# Quectel-2560-v2_2.net
KiCad netlist of a schematic drawn in EAGLE
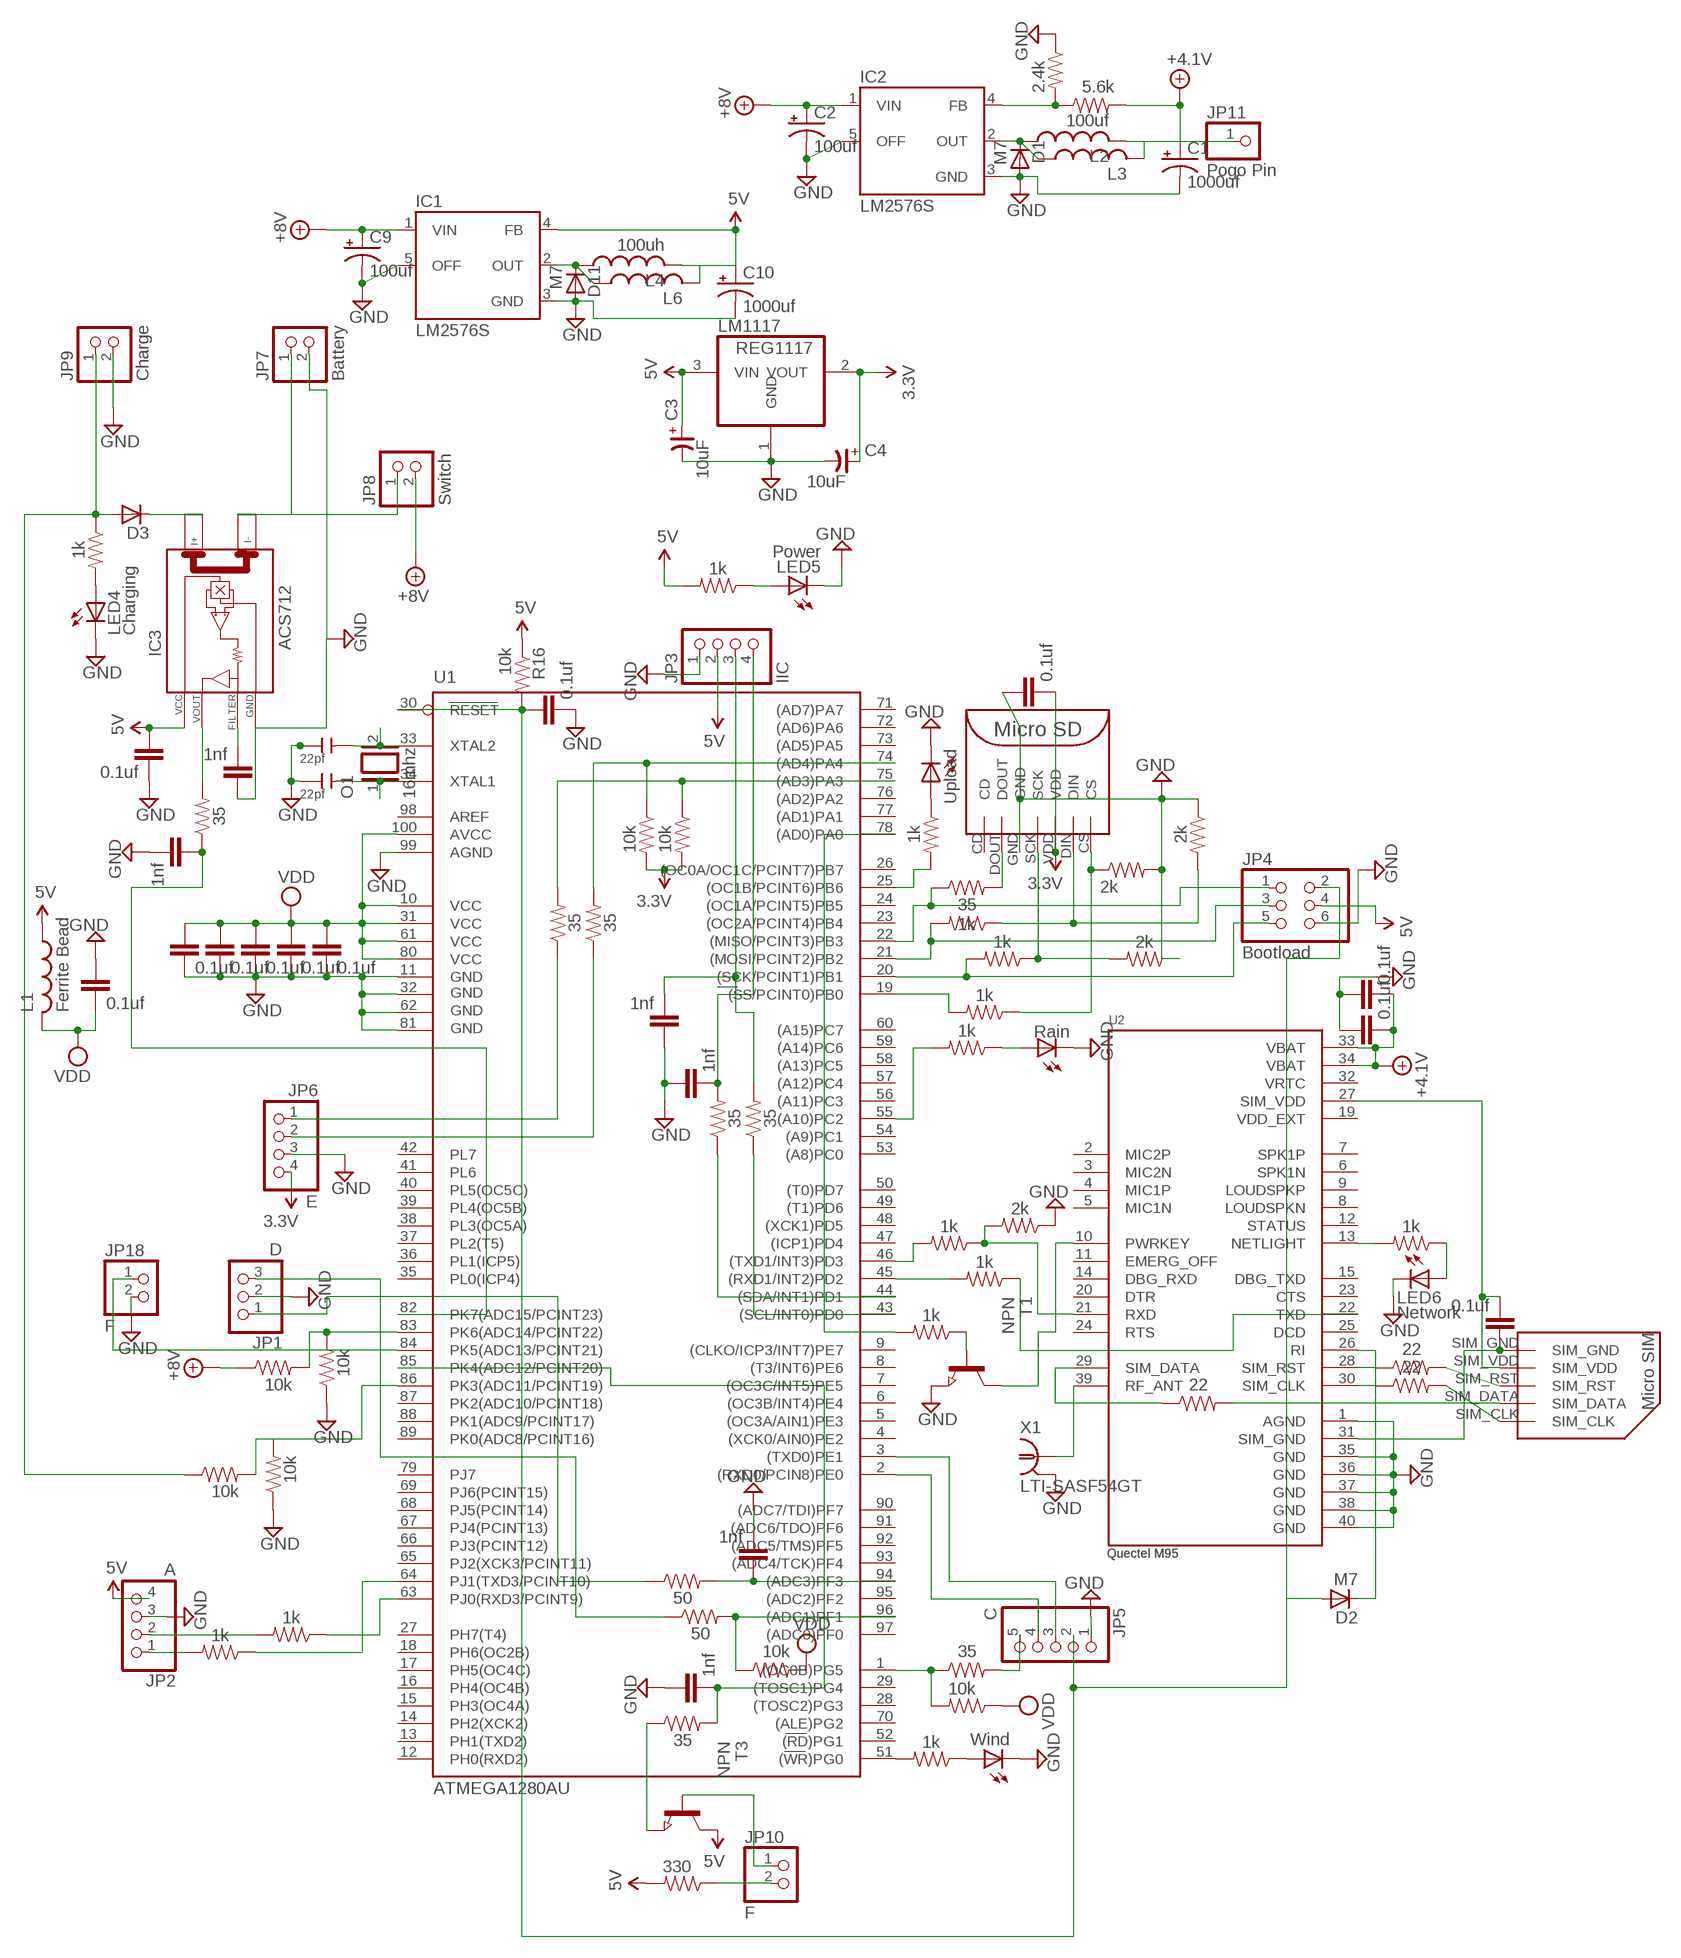
[diagram p0: schematic, sheet 1]

(export (version "E")
  (design (tool "Eeschema 10.0.6"))
  (components
    (comp (ref "C1")
      (value "1000uf")
      (footprint "eagle-import:153CLV-1012")
      (libsource (lib "eagle-import") (part "CPOL-US153CLV-1012"))
    )
    (comp (ref "C2")
      (value "100uf")
      (footprint "eagle-import:CT7343")
      (libsource (lib "eagle-import") (part "CPOL-USCT7343"))
    )
    (comp (ref "C3")
      (value "10uF")
      (footprint "eagle-import:3528_T")
      (libsource (lib "eagle-import") (part "CP-3528"))
    )
    (comp (ref "C4")
      (value "10uF")
      (footprint "eagle-import:3528_T")
      (libsource (lib "eagle-import") (part "CP-3528"))
    )
    (comp (ref "C7")
      (value "22pf")
      (footprint "eagle-import:C0805")
      (fields (field (name "MPN") "CC0805JRNPO9BN220"))
      (libsource (lib "eagle-import") (part "CERAMIC-22PF-50V-5%-NPO(0805)"))
    )
    (comp (ref "C8")
      (value "22pf")
      (footprint "eagle-import:C0805")
      (fields (field (name "MPN") "CC0805JRNPO9BN220"))
      (libsource (lib "eagle-import") (part "CERAMIC-22PF-50V-5%-NPO(0805)"))
    )
    (comp (ref "C9")
      (value "100uf")
      (footprint "eagle-import:CT7343")
      (libsource (lib "eagle-import") (part "CPOL-USCT7343"))
    )
    (comp (ref "C10")
      (value "1000uf")
      (footprint "eagle-import:153CLV-1012")
      (libsource (lib "eagle-import") (part "CPOL-US153CLV-1012"))
    )
    (comp (ref "D1")
      (value "M7")
      (footprint "eagle-import:SOD106A")
      (fields (field (name "MPN") "BYS10/45"))
      (libsource (lib "eagle-import") (part "BYS10"))
    )
    (comp (ref "D2")
      (value "M7")
      (footprint "eagle-import:SOD106A")
      (fields (field (name "MPN") "BYS10/45"))
      (libsource (lib "eagle-import") (part "BYS10"))
    )
    (comp (ref "D3")
      (value "BYS10")
      (footprint "eagle-import:SOD106A")
      (fields (field (name "MPN") "BYS10/45"))
      (libsource (lib "eagle-import") (part "BYS10"))
    )
    (comp (ref "D11")
      (value "M7")
      (footprint "eagle-import:SOD106A")
      (fields (field (name "MPN") "BYS10/45"))
      (libsource (lib "eagle-import") (part "BYS10"))
    )
    (comp (ref "DC1")
      (value "0.1uf")
      (footprint "eagle-import:C0805")
      (libsource (lib "eagle-import") (part "C-EUC0805"))
    )
    (comp (ref "DC2")
      (value "0.1uf")
      (footprint "eagle-import:C0805")
      (libsource (lib "eagle-import") (part "C-EUC0805"))
    )
    (comp (ref "DC3")
      (value "0.1uf")
      (footprint "eagle-import:C0805")
      (libsource (lib "eagle-import") (part "C-EUC0805"))
    )
    (comp (ref "DC4")
      (value "0.1uf")
      (footprint "eagle-import:C0805")
      (libsource (lib "eagle-import") (part "C-EUC0805"))
    )
    (comp (ref "DC5")
      (value "0.1uf")
      (footprint "eagle-import:C0805")
      (libsource (lib "eagle-import") (part "C-EUC0805"))
    )
    (comp (ref "DC6")
      (value "0.1uf")
      (footprint "eagle-import:C0805")
      (libsource (lib "eagle-import") (part "C-EUC0805"))
    )
    (comp (ref "DC7")
      (value "0.1uf")
      (footprint "eagle-import:C0805")
      (libsource (lib "eagle-import") (part "C-EUC0805"))
    )
    (comp (ref "DC10")
      (value "0.1uf")
      (footprint "eagle-import:C0805")
      (libsource (lib "eagle-import") (part "C-EUC0805"))
    )
    (comp (ref "DC11")
      (value "0.1uf")
      (footprint "eagle-import:C0805")
      (libsource (lib "eagle-import") (part "C-EUC0805"))
    )
    (comp (ref "DC12")
      (value "1nf")
      (footprint "eagle-import:C0805")
      (libsource (lib "eagle-import") (part "C-EUC0805"))
    )
    (comp (ref "DC13")
      (value "1nf")
      (footprint "eagle-import:C0805")
      (libsource (lib "eagle-import") (part "C-EUC0805"))
    )
    (comp (ref "DC14")
      (value "1nf")
      (footprint "eagle-import:C0805")
      (libsource (lib "eagle-import") (part "C-EUC0805"))
    )
    (comp (ref "DC15")
      (value "0.1uf")
      (footprint "eagle-import:C0805")
      (libsource (lib "eagle-import") (part "C-EUC0805"))
    )
    (comp (ref "DC17")
      (value "1nf")
      (footprint "eagle-import:C0805")
      (libsource (lib "eagle-import") (part "C-EUC0805"))
    )
    (comp (ref "DC18")
      (value "0.1uf")
      (footprint "eagle-import:C0805")
      (libsource (lib "eagle-import") (part "C-EUC0805"))
    )
    (comp (ref "DC19")
      (value "0.1uf")
      (footprint "eagle-import:C0805")
      (libsource (lib "eagle-import") (part "C-EUC0805"))
    )
    (comp (ref "DC20")
      (value "1nf")
      (footprint "eagle-import:C0805")
      (libsource (lib "eagle-import") (part "C-EUC0805"))
    )
    (comp (ref "DC21")
      (value "1nf")
      (footprint "eagle-import:C0805")
      (libsource (lib "eagle-import") (part "C-EUC0805"))
    )
    (comp (ref "IC1")
      (value "LM2576S")
      (footprint "eagle-import:TO263-5")
      (libsource (lib "eagle-import") (part "LM2576S"))
    )
    (comp (ref "IC2")
      (value "LM2576S")
      (footprint "eagle-import:TO263-5")
      (libsource (lib "eagle-import") (part "LM2576S"))
    )
    (comp (ref "IC3")
      (value "ACS712")
      (footprint "eagle-import:SO08")
      (libsource (lib "eagle-import") (part "ACS712"))
    )
    (comp (ref "JP1")
      (value "D")
      (footprint "eagle-import:1X03")
      (libsource (lib "eagle-import") (part "PINHD-1X3"))
    )
    (comp (ref "JP2")
      (value "A")
      (footprint "eagle-import:1X04")
      (libsource (lib "eagle-import") (part "PINHD-1X4"))
    )
    (comp (ref "JP3")
      (value "IIC")
      (footprint "eagle-import:1X04")
      (libsource (lib "eagle-import") (part "PINHD-1X4"))
    )
    (comp (ref "JP4")
      (value "Bootload")
      (footprint "eagle-import:2X03")
      (libsource (lib "eagle-import") (part "PINHD-2X3"))
    )
    (comp (ref "JP5")
      (value "C")
      (footprint "eagle-import:1X05")
      (libsource (lib "eagle-import") (part "PINHD-1X5"))
    )
    (comp (ref "JP6")
      (value "E")
      (footprint "eagle-import:1X04")
      (libsource (lib "eagle-import") (part "PINHD-1X4"))
    )
    (comp (ref "JP7")
      (value "Battery")
      (footprint "eagle-import:1X02")
      (libsource (lib "eagle-import") (part "PINHD-1X2"))
    )
    (comp (ref "JP8")
      (value "Switch")
      (footprint "eagle-import:1X02")
      (libsource (lib "eagle-import") (part "PINHD-1X2"))
    )
    (comp (ref "JP9")
      (value "Charge")
      (footprint "eagle-import:1X02")
      (libsource (lib "eagle-import") (part "PINHD-1X2"))
    )
    (comp (ref "JP10")
      (value "F")
      (footprint "eagle-import:1X02")
      (libsource (lib "eagle-import") (part "PINHD-1X2"))
    )
    (comp (ref "JP11")
      (value "Pogo Pin")
      (footprint "eagle-import:1X01")
      (libsource (lib "eagle-import") (part "PINHD-1X1"))
    )
    (comp (ref "JP18")
      (value "F")
      (footprint "eagle-import:1X02")
      (libsource (lib "eagle-import") (part "PINHD-1X2"))
    )
    (comp (ref "L1")
      (value "Ferrite Bead")
      (footprint "eagle-import:L2012C")
      (libsource (lib "eagle-import") (part "L-USL2012C"))
    )
    (comp (ref "L2")
      (value "100uf")
      (footprint "eagle-import:PIS2816")
      (libsource (lib "eagle-import") (part "L-USPIS2816"))
    )
    (comp (ref "L3")
      (value "L-US6000-XXX-RC")
      (footprint "eagle-import:6000-XXXX-RC")
      (libsource (lib "eagle-import") (part "L-US6000-XXX-RC"))
    )
    (comp (ref "L4")
      (value "100uh")
      (footprint "eagle-import:PIS2816")
      (libsource (lib "eagle-import") (part "L-USPIS2816"))
    )
    (comp (ref "L6")
      (value "L-US6000-XXX-RC")
      (footprint "eagle-import:6000-XXXX-RC")
      (libsource (lib "eagle-import") (part "L-US6000-XXX-RC"))
    )
    (comp (ref "LED1")
      (value "Rain")
      (footprint "eagle-import:CHIP-LED0805")
      (libsource (lib "eagle-import") (part "LEDCHIP-LED0805"))
    )
    (comp (ref "LED2")
      (value "Upload")
      (footprint "eagle-import:CHIP-LED0805")
      (libsource (lib "eagle-import") (part "LEDCHIP-LED0805"))
    )
    (comp (ref "LED3")
      (value "Wind")
      (footprint "eagle-import:CHIP-LED0805")
      (libsource (lib "eagle-import") (part "LEDCHIP-LED0805"))
    )
    (comp (ref "LED4")
      (value "Charging")
      (footprint "eagle-import:CHIP-LED0805")
      (libsource (lib "eagle-import") (part "LEDCHIP-LED0805"))
    )
    (comp (ref "LED5")
      (value "Power")
      (footprint "eagle-import:CHIP-LED0805")
      (libsource (lib "eagle-import") (part "LEDCHIP-LED0805"))
    )
    (comp (ref "LED6")
      (value "Network")
      (footprint "eagle-import:CHIP-LED0805")
      (libsource (lib "eagle-import") (part "LEDCHIP-LED0805"))
    )
    (comp (ref "LM1117")
      (value "REG1117")
      (footprint "eagle-import:SOT223")
      (libsource (lib "eagle-import") (part "REG1117"))
    )
    (comp (ref "O1")
      (value "16mhz")
      (footprint "eagle-import:QS")
      (libsource (lib "eagle-import") (part "XTAL/S"))
    )
    (comp (ref "R1")
      (value "35")
      (footprint "eagle-import:0805")
      (libsource (lib "eagle-import") (part "RESISTOR0805-RES"))
    )
    (comp (ref "R2")
      (value "10k")
      (footprint "eagle-import:0805")
      (libsource (lib "eagle-import") (part "RESISTOR0805-RES"))
    )
    (comp (ref "R3")
      (value "10k")
      (footprint "eagle-import:0805")
      (libsource (lib "eagle-import") (part "RESISTOR0805-RES"))
    )
    (comp (ref "R4")
      (value "1k")
      (footprint "eagle-import:0805")
      (libsource (lib "eagle-import") (part "RESISTOR0805-RES"))
    )
    (comp (ref "R5")
      (value "35")
      (footprint "eagle-import:0805")
      (libsource (lib "eagle-import") (part "RESISTOR0805-RES"))
    )
    (comp (ref "R6")
      (value "1k")
      (footprint "eagle-import:0805")
      (libsource (lib "eagle-import") (part "RESISTOR0805-RES"))
    )
    (comp (ref "R7")
      (value "1k")
      (footprint "eagle-import:0805")
      (libsource (lib "eagle-import") (part "RESISTOR0805-RES"))
    )
    (comp (ref "R8")
      (value "1k")
      (footprint "eagle-import:0805")
      (libsource (lib "eagle-import") (part "RESISTOR0805-RES"))
    )
    (comp (ref "R9")
      (value "2k")
      (footprint "eagle-import:0805")
      (libsource (lib "eagle-import") (part "RESISTOR0805-RES"))
    )
    (comp (ref "R10")
      (value "22")
      (footprint "eagle-import:0805")
      (libsource (lib "eagle-import") (part "RESISTOR0805-RES"))
    )
    (comp (ref "R11")
      (value "22")
      (footprint "eagle-import:0805")
      (libsource (lib "eagle-import") (part "RESISTOR0805-RES"))
    )
    (comp (ref "R14")
      (value "1k")
      (footprint "eagle-import:0805")
      (libsource (lib "eagle-import") (part "RESISTOR0805-RES"))
    )
    (comp (ref "R15")
      (value "1k")
      (footprint "eagle-import:0805")
      (libsource (lib "eagle-import") (part "RESISTOR0805-RES"))
    )
    (comp (ref "R16")
      (value "10k")
      (footprint "eagle-import:0805")
      (libsource (lib "eagle-import") (part "RESISTOR0805-RES"))
    )
    (comp (ref "R17")
      (value "1k")
      (footprint "eagle-import:0805")
      (libsource (lib "eagle-import") (part "RESISTOR0805-RES"))
    )
    (comp (ref "R18")
      (value "1k")
      (footprint "eagle-import:0805")
      (libsource (lib "eagle-import") (part "RESISTOR0805-RES"))
    )
    (comp (ref "R19")
      (value "35")
      (footprint "eagle-import:0805")
      (libsource (lib "eagle-import") (part "RESISTOR0805-RES"))
    )
    (comp (ref "R20")
      (value "10k")
      (footprint "eagle-import:0805")
      (libsource (lib "eagle-import") (part "RESISTOR0805-RES"))
    )
    (comp (ref "R21")
      (value "50")
      (footprint "eagle-import:0805")
      (libsource (lib "eagle-import") (part "RESISTOR0805-RES"))
    )
    (comp (ref "R22")
      (value "35")
      (footprint "eagle-import:0805")
      (libsource (lib "eagle-import") (part "RESISTOR0805-RES"))
    )
    (comp (ref "R23")
      (value "2k")
      (footprint "eagle-import:0805")
      (libsource (lib "eagle-import") (part "RESISTOR0805-RES"))
    )
    (comp (ref "R24")
      (value "2k")
      (footprint "eagle-import:0805")
      (libsource (lib "eagle-import") (part "RESISTOR0805-RES"))
    )
    (comp (ref "R25")
      (value "1k")
      (footprint "eagle-import:0805")
      (libsource (lib "eagle-import") (part "RESISTOR0805-RES"))
    )
    (comp (ref "R26")
      (value "1k")
      (footprint "eagle-import:0805")
      (libsource (lib "eagle-import") (part "RESISTOR0805-RES"))
    )
    (comp (ref "R27")
      (value "1k")
      (footprint "eagle-import:0805")
      (libsource (lib "eagle-import") (part "RESISTOR0805-RES"))
    )
    (comp (ref "R28")
      (value "1k")
      (footprint "eagle-import:0805")
      (libsource (lib "eagle-import") (part "RESISTOR0805-RES"))
    )
    (comp (ref "R29")
      (value "2k")
      (footprint "eagle-import:0805")
      (libsource (lib "eagle-import") (part "RESISTOR0805-RES"))
    )
    (comp (ref "R30")
      (value "35")
      (footprint "eagle-import:0805")
      (libsource (lib "eagle-import") (part "RESISTOR0805-RES"))
    )
    (comp (ref "R31")
      (value "50")
      (footprint "eagle-import:0805")
      (libsource (lib "eagle-import") (part "RESISTOR0805-RES"))
    )
    (comp (ref "R32")
      (value "1k")
      (footprint "eagle-import:0805")
      (libsource (lib "eagle-import") (part "RESISTOR0805-RES"))
    )
    (comp (ref "R33")
      (value "1k")
      (footprint "eagle-import:0805")
      (libsource (lib "eagle-import") (part "RESISTOR0805-RES"))
    )
    (comp (ref "R34")
      (value "10k")
      (footprint "eagle-import:0805")
      (libsource (lib "eagle-import") (part "RESISTOR0805-RES"))
    )
    (comp (ref "R35")
      (value "35")
      (footprint "eagle-import:0805")
      (libsource (lib "eagle-import") (part "RESISTOR0805-RES"))
    )
    (comp (ref "R36")
      (value "10k")
      (footprint "eagle-import:0805")
      (libsource (lib "eagle-import") (part "RESISTOR0805-RES"))
    )
    (comp (ref "R39")
      (value "35")
      (footprint "eagle-import:0805")
      (libsource (lib "eagle-import") (part "RESISTOR0805-RES"))
    )
    (comp (ref "R40")
      (value "10k")
      (footprint "eagle-import:0805")
      (libsource (lib "eagle-import") (part "RESISTOR0805-RES"))
    )
    (comp (ref "R41")
      (value "330")
      (footprint "eagle-import:0805")
      (libsource (lib "eagle-import") (part "RESISTOR0805-RES"))
    )
    (comp (ref "R42")
      (value "35")
      (footprint "eagle-import:0805")
      (libsource (lib "eagle-import") (part "RESISTOR0805-RES"))
    )
    (comp (ref "R43")
      (value "10k")
      (footprint "eagle-import:0805")
      (libsource (lib "eagle-import") (part "RESISTOR0805-RES"))
    )
    (comp (ref "R44")
      (value "10k")
      (footprint "eagle-import:0805")
      (libsource (lib "eagle-import") (part "RESISTOR0805-RES"))
    )
    (comp (ref "R45")
      (value "2.4k")
      (footprint "eagle-import:0805")
      (libsource (lib "eagle-import") (part "RESISTOR0805-RES"))
    )
    (comp (ref "R46")
      (value "5.6k")
      (footprint "eagle-import:0805")
      (libsource (lib "eagle-import") (part "RESISTOR0805-RES"))
    )
    (comp (ref "R47")
      (value "22")
      (footprint "eagle-import:0805")
      (libsource (lib "eagle-import") (part "RESISTOR0805-RES"))
    )
    (comp (ref "T1")
      (value "NPN")
      (footprint "eagle-import:SOT23")
      (libsource (lib "eagle-import") (part "NPN-TRANSISTOR_SOT23"))
    )
    (comp (ref "T3")
      (value "NPN")
      (footprint "eagle-import:SOT23")
      (libsource (lib "eagle-import") (part "NPN-TRANSISTOR_SOT23"))
    )
    (comp (ref "U$1")
      (value "MICROSD")
      (footprint "eagle-import:MICROSD")
      (libsource (lib "eagle-import") (part "MICROSD"))
    )
    (comp (ref "U$2")
      (value "MICROSIM")
      (footprint "eagle-import:MICROSIM")
      (libsource (lib "eagle-import") (part "MICROSIM"))
    )
    (comp (ref "U1")
      (value "ATMEGA1280AU")
      (footprint "eagle-import:TQFP100")
      (libsource (lib "eagle-import") (part "ATMEGA2560AU"))
    )
    (comp (ref "U2")
      (value "Quectel M95")
      (footprint "eagle-import:XCVR_M95")
      (libsource (lib "eagle-import") (part "M95"))
    )
    (comp (ref "X1")
      (value "LTI-SASF54GT")
      (footprint "eagle-import:LTI-SASF54GT")
      (libsource (lib "eagle-import") (part "LTI-SASF54GT"))
    )
  )
  (nets
    (net (code "1") (name "+4.1V") (class "Default")
      (node (ref "C1") (pin "+") (pinfunction "+_+") (pintype "passive"))
      (node (ref "DC6") (pin "2") (pinfunction "2_2") (pintype "passive"))
      (node (ref "DC7") (pin "2") (pinfunction "2_2") (pintype "passive"))
      (node (ref "JP11") (pin "1") (pinfunction "1_1") (pintype "passive"))
      (node (ref "L2") (pin "2") (pinfunction "2_2") (pintype "passive"))
      (node (ref "L3") (pin "2") (pinfunction "2_2") (pintype "passive"))
      (node (ref "R46") (pin "2") (pinfunction "2_2") (pintype "passive"))
      (node (ref "U2") (pin "33") (pinfunction "VBAT_33") (pintype "power_in"))
      (node (ref "U2") (pin "34") (pinfunction "VBAT_34") (pintype "power_in"))
    )
    (net (code "2") (name "+8V") (class "Default")
      (node (ref "C2") (pin "+") (pinfunction "+_+") (pintype "passive"))
      (node (ref "C9") (pin "+") (pinfunction "+_+") (pintype "passive"))
      (node (ref "IC1") (pin "1") (pinfunction "VIN_1") (pintype "power_in"))
      (node (ref "IC2") (pin "1") (pinfunction "VIN_1") (pintype "power_in"))
      (node (ref "JP8") (pin "2") (pinfunction "2_2") (pintype "passive"))
      (node (ref "R43") (pin "1") (pinfunction "1_1") (pintype "passive"))
    )
    (net (code "3") (name "/VDD_EXT") (class "Default")
      (node (ref "U2") (pin "19") (pinfunction "VDD_EXT_19") (pintype "power_in"))
    )
    (net (code "4") (name "/VRTC") (class "Default")
      (node (ref "U2") (pin "32") (pinfunction "VRTC_32") (pintype "power_in"))
    )
    (net (code "5") (name "3.3V") (class "Default")
      (node (ref "C4") (pin "+") (pinfunction "+_+") (pintype "passive"))
      (node (ref "DC10") (pin "2") (pinfunction "2_2") (pintype "passive"))
      (node (ref "JP6") (pin "4") (pinfunction "4_4") (pintype "passive"))
      (node (ref "LM1117") (pin "2") (pinfunction "VOUT_2") (pintype "output"))
      (node (ref "R34") (pin "2") (pinfunction "2_2") (pintype "passive"))
      (node (ref "R36") (pin "2") (pinfunction "2_2") (pintype "passive"))
      (node (ref "U$1") (pin "VDD") (pinfunction "VDD_VDD") (pintype "power_in"))
    )
    (net (code "6") (name "5V") (class "Default")
      (node (ref "C10") (pin "+") (pinfunction "+_+") (pintype "passive"))
      (node (ref "C3") (pin "+") (pinfunction "+_+") (pintype "passive"))
      (node (ref "DC19") (pin "2") (pinfunction "2_2") (pintype "passive"))
      (node (ref "IC1") (pin "4") (pinfunction "FB_4") (pintype "input"))
      (node (ref "IC3") (pin "8") (pinfunction "VCC_8") (pintype "power_in"))
      (node (ref "JP2") (pin "4") (pinfunction "4_4") (pintype "passive"))
      (node (ref "JP3") (pin "2") (pinfunction "2_2") (pintype "passive"))
      (node (ref "JP4") (pin "4") (pinfunction "4_4") (pintype "passive"))
      (node (ref "L1") (pin "1") (pinfunction "1_1") (pintype "passive"))
      (node (ref "L4") (pin "2") (pinfunction "2_2") (pintype "passive"))
      (node (ref "L6") (pin "2") (pinfunction "2_2") (pintype "passive"))
      (node (ref "LM1117") (pin "3") (pinfunction "VIN_3") (pintype "input"))
      (node (ref "R16") (pin "1") (pinfunction "1_1") (pintype "passive"))
      (node (ref "R18") (pin "2") (pinfunction "2_2") (pintype "passive"))
      (node (ref "R41") (pin "2") (pinfunction "2_2") (pintype "passive"))
      (node (ref "T3") (pin "3") (pinfunction "C_3") (pintype "passive"))
    )
    (net (code "7") (name "GND") (class "Default")
      (node (ref "C1") (pin "-") (pinfunction "-_-") (pintype "passive"))
      (node (ref "C10") (pin "-") (pinfunction "-_-") (pintype "passive"))
      (node (ref "C2") (pin "-") (pinfunction "-_-") (pintype "passive"))
      (node (ref "C3") (pin "-") (pinfunction "-_-") (pintype "passive"))
      (node (ref "C4") (pin "-") (pinfunction "-_-") (pintype "passive"))
      (node (ref "C7") (pin "1") (pinfunction "1_1") (pintype "passive"))
      (node (ref "C8") (pin "1") (pinfunction "1_1") (pintype "passive"))
      (node (ref "C9") (pin "-") (pinfunction "-_-") (pintype "passive"))
      (node (ref "D1") (pin "A") (pinfunction "A_A") (pintype "passive"))
      (node (ref "D11") (pin "A") (pinfunction "A_A") (pintype "passive"))
      (node (ref "DC1") (pin "2") (pinfunction "2_2") (pintype "passive"))
      (node (ref "DC10") (pin "1") (pinfunction "1_1") (pintype "passive"))
      (node (ref "DC11") (pin "2") (pinfunction "2_2") (pintype "passive"))
      (node (ref "DC12") (pin "1") (pinfunction "1_1") (pintype "passive"))
      (node (ref "DC13") (pin "1") (pinfunction "1_1") (pintype "passive"))
      (node (ref "DC14") (pin "1") (pinfunction "1_1") (pintype "passive"))
      (node (ref "DC17") (pin "2") (pinfunction "2_2") (pintype "passive"))
      (node (ref "DC18") (pin "1") (pinfunction "1_1") (pintype "passive"))
      (node (ref "DC19") (pin "1") (pinfunction "1_1") (pintype "passive"))
      (node (ref "DC2") (pin "2") (pinfunction "2_2") (pintype "passive"))
      (node (ref "DC20") (pin "1") (pinfunction "1_1") (pintype "passive"))
      (node (ref "DC21") (pin "2") (pinfunction "2_2") (pintype "passive"))
      (node (ref "DC3") (pin "2") (pinfunction "2_2") (pintype "passive"))
      (node (ref "DC4") (pin "2") (pinfunction "2_2") (pintype "passive"))
      (node (ref "DC5") (pin "2") (pinfunction "2_2") (pintype "passive"))
      (node (ref "DC6") (pin "1") (pinfunction "1_1") (pintype "passive"))
      (node (ref "DC7") (pin "1") (pinfunction "1_1") (pintype "passive"))
      (node (ref "IC1") (pin "3") (pinfunction "GND_3") (pintype "power_in"))
      (node (ref "IC1") (pin "5") (pinfunction "OFF_5") (pintype "input"))
      (node (ref "IC2") (pin "3") (pinfunction "GND_3") (pintype "power_in"))
      (node (ref "IC2") (pin "5") (pinfunction "OFF_5") (pintype "input"))
      (node (ref "IC3") (pin "5") (pinfunction "GND_5") (pintype "power_in"))
      (node (ref "JP1") (pin "2") (pinfunction "2_2") (pintype "passive"))
      (node (ref "JP18") (pin "2") (pinfunction "2_2") (pintype "passive"))
      (node (ref "JP2") (pin "3") (pinfunction "3_3") (pintype "passive"))
      (node (ref "JP3") (pin "1") (pinfunction "1_1") (pintype "passive"))
      (node (ref "JP4") (pin "6") (pinfunction "6_6") (pintype "passive"))
      (node (ref "JP5") (pin "1") (pinfunction "1_1") (pintype "passive"))
      (node (ref "JP6") (pin "3") (pinfunction "3_3") (pintype "passive"))
      (node (ref "JP7") (pin "2") (pinfunction "2_2") (pintype "passive"))
      (node (ref "JP9") (pin "2") (pinfunction "2_2") (pintype "passive"))
      (node (ref "LED1") (pin "C") (pinfunction "C_C") (pintype "passive"))
      (node (ref "LED2") (pin "C") (pinfunction "C_C") (pintype "passive"))
      (node (ref "LED3") (pin "C") (pinfunction "C_C") (pintype "passive"))
      (node (ref "LED4") (pin "C") (pinfunction "C_C") (pintype "passive"))
      (node (ref "LED5") (pin "C") (pinfunction "C_C") (pintype "passive"))
      (node (ref "LED6") (pin "C") (pinfunction "C_C") (pintype "passive"))
      (node (ref "LM1117") (pin "1") (pinfunction "GND_1") (pintype "power_in"))
      (node (ref "R23") (pin "2") (pinfunction "2_2") (pintype "passive"))
      (node (ref "R24") (pin "1") (pinfunction "1_1") (pintype "passive"))
      (node (ref "R29") (pin "1") (pinfunction "1_1") (pintype "passive"))
      (node (ref "R3") (pin "1") (pinfunction "1_1") (pintype "passive"))
      (node (ref "R44") (pin "1") (pinfunction "1_1") (pintype "passive"))
      (node (ref "R45") (pin "1") (pinfunction "1_1") (pintype "passive"))
      (node (ref "R9") (pin "1") (pinfunction "1_1") (pintype "passive"))
      (node (ref "T1") (pin "2") (pinfunction "E_2") (pintype "passive"))
      (node (ref "U$1") (pin "GND") (pinfunction "GND_GND") (pintype "power_in"))
      (node (ref "U1") (pin "11") (pinfunction "GND_11") (pintype "power_in"))
      (node (ref "U1") (pin "32") (pinfunction "GND1_32") (pintype "power_in"))
      (node (ref "U1") (pin "62") (pinfunction "GND2_62") (pintype "power_in"))
      (node (ref "U1") (pin "81") (pinfunction "GND3_81") (pintype "power_in"))
      (node (ref "U1") (pin "99") (pinfunction "AGND_99") (pintype "power_in"))
      (node (ref "U2") (pin "1") (pinfunction "AGND_1") (pintype "power_in"))
      (node (ref "U2") (pin "35") (pinfunction "GND_35") (pintype "power_in"))
      (node (ref "U2") (pin "36") (pinfunction "GND_36") (pintype "power_in"))
      (node (ref "U2") (pin "37") (pinfunction "GND_37") (pintype "power_in"))
      (node (ref "U2") (pin "38") (pinfunction "GND_38") (pintype "input"))
      (node (ref "U2") (pin "40") (pinfunction "GND_40") (pintype "power_in"))
      (node (ref "X1") (pin "2") (pinfunction "2_2") (pintype "passive"))
      (node (ref "X1") (pin "3") (pinfunction "2_3") (pintype "passive"))
      (node (ref "X1") (pin "4") (pinfunction "2_4") (pintype "passive"))
      (node (ref "X1") (pin "5") (pinfunction "2_5") (pintype "passive"))
    )
    (net (code "8") (name "Net-(D3-PadA)") (class "Default")
      (node (ref "D3") (pin "A") (pinfunction "A_A") (pintype "passive"))
      (node (ref "JP9") (pin "1") (pinfunction "1_1") (pintype "passive"))
      (node (ref "R2") (pin "1") (pinfunction "1_1") (pintype "passive"))
      (node (ref "R26") (pin "1") (pinfunction "1_1") (pintype "passive"))
    )
    (net (code "9") (name "Net-(DC12-Pad2)") (class "Default")
      (node (ref "DC12") (pin "2") (pinfunction "2_2") (pintype "passive"))
      (node (ref "JP3") (pin "4") (pinfunction "4_4") (pintype "passive"))
      (node (ref "R5") (pin "2") (pinfunction "2_2") (pintype "passive"))
    )
    (net (code "10") (name "Net-(DC13-Pad2)") (class "Default")
      (node (ref "DC13") (pin "2") (pinfunction "2_2") (pintype "passive"))
      (node (ref "JP3") (pin "3") (pinfunction "3_3") (pintype "passive"))
      (node (ref "R30") (pin "2") (pinfunction "2_2") (pintype "passive"))
    )
    (net (code "11") (name "Net-(IC1-OUT)") (class "Default")
      (node (ref "D11") (pin "K") (pinfunction "K_K") (pintype "passive"))
      (node (ref "IC1") (pin "2") (pinfunction "OUT_2") (pintype "output"))
      (node (ref "L4") (pin "1") (pinfunction "1_1") (pintype "passive"))
      (node (ref "L6") (pin "1") (pinfunction "1_1") (pintype "passive"))
    )
    (net (code "12") (name "Net-(IC2-FB)") (class "Default")
      (node (ref "IC2") (pin "4") (pinfunction "FB_4") (pintype "input"))
      (node (ref "R45") (pin "2") (pinfunction "2_2") (pintype "passive"))
      (node (ref "R46") (pin "1") (pinfunction "1_1") (pintype "passive"))
    )
    (net (code "13") (name "Net-(IC2-OUT)") (class "Default")
      (node (ref "D1") (pin "K") (pinfunction "K_K") (pintype "passive"))
      (node (ref "IC2") (pin "2") (pinfunction "OUT_2") (pintype "output"))
      (node (ref "L2") (pin "1") (pinfunction "1_1") (pintype "passive"))
      (node (ref "L3") (pin "1") (pinfunction "1_1") (pintype "passive"))
    )
    (net (code "14") (name "Net-(IC3-FILTER)") (class "Default")
      (node (ref "DC20") (pin "2") (pinfunction "2_2") (pintype "passive"))
      (node (ref "IC3") (pin "6") (pinfunction "FILTER_6") (pintype "bidirectional"))
    )
    (net (code "15") (name "Net-(IC3-I+_0)") (class "Default")
      (node (ref "D3") (pin "K") (pinfunction "K_K") (pintype "passive"))
      (node (ref "IC3") (pin "1") (pinfunction "I+_0_1") (pintype "bidirectional"))
    )
    (net (code "16") (name "Net-(IC3-I-_1)") (class "Default")
      (node (ref "IC3") (pin "4") (pinfunction "I-_1_4") (pintype "bidirectional"))
      (node (ref "JP7") (pin "1") (pinfunction "1_1") (pintype "passive"))
      (node (ref "JP8") (pin "1") (pinfunction "1_1") (pintype "passive"))
    )
    (net (code "17") (name "Net-(IC3-VOUT)") (class "Default")
      (node (ref "IC3") (pin "7") (pinfunction "VOUT_7") (pintype "output"))
      (node (ref "R1") (pin "2") (pinfunction "2_2") (pintype "passive"))
    )
    (net (code "18") (name "Net-(JP1-Pad1)") (class "Default")
      (node (ref "JP1") (pin "1") (pinfunction "1_1") (pintype "passive"))
      (node (ref "R21") (pin "1") (pinfunction "1_1") (pintype "passive"))
    )
    (net (code "19") (name "Net-(JP1-Pad3)") (class "Default")
      (node (ref "JP1") (pin "3") (pinfunction "3_3") (pintype "passive"))
      (node (ref "R31") (pin "1") (pinfunction "1_1") (pintype "passive"))
    )
    (net (code "20") (name "Net-(JP2-Pad1)") (class "Default")
      (node (ref "JP2") (pin "1") (pinfunction "1_1") (pintype "passive"))
      (node (ref "R33") (pin "2") (pinfunction "2_2") (pintype "passive"))
    )
    (net (code "21") (name "Net-(JP2-Pad2)") (class "Default")
      (node (ref "JP2") (pin "2") (pinfunction "2_2") (pintype "passive"))
      (node (ref "R32") (pin "2") (pinfunction "2_2") (pintype "passive"))
    )
    (net (code "22") (name "Net-(JP5-Pad5)") (class "Default")
      (node (ref "JP5") (pin "5") (pinfunction "5_5") (pintype "passive"))
      (node (ref "R39") (pin "2") (pinfunction "2_2") (pintype "passive"))
    )
    (net (code "23") (name "Net-(JP6-Pad1)") (class "Default")
      (node (ref "JP6") (pin "1") (pinfunction "1_1") (pintype "passive"))
      (node (ref "R22") (pin "1") (pinfunction "1_1") (pintype "passive"))
    )
    (net (code "24") (name "Net-(JP6-Pad2)") (class "Default")
      (node (ref "JP6") (pin "2") (pinfunction "2_2") (pintype "passive"))
      (node (ref "R19") (pin "1") (pinfunction "1_1") (pintype "passive"))
    )
    (net (code "25") (name "Net-(JP10-Pad2)") (class "Default")
      (node (ref "JP10") (pin "2") (pinfunction "2_2") (pintype "passive"))
      (node (ref "R41") (pin "1") (pinfunction "1_1") (pintype "passive"))
    )
    (net (code "26") (name "Net-(LED1-PadA)") (class "Default")
      (node (ref "LED1") (pin "A") (pinfunction "A_A") (pintype "passive"))
      (node (ref "R27") (pin "1") (pinfunction "1_1") (pintype "passive"))
    )
    (net (code "27") (name "Net-(LED2-PadA)") (class "Default")
      (node (ref "LED2") (pin "A") (pinfunction "A_A") (pintype "passive"))
      (node (ref "R25") (pin "1") (pinfunction "1_1") (pintype "passive"))
    )
    (net (code "28") (name "Net-(LED3-PadA)") (class "Default")
      (node (ref "LED3") (pin "A") (pinfunction "A_A") (pintype "passive"))
      (node (ref "R28") (pin "1") (pinfunction "1_1") (pintype "passive"))
    )
    (net (code "29") (name "Net-(LED4-PadA)") (class "Default")
      (node (ref "LED4") (pin "A") (pinfunction "A_A") (pintype "passive"))
      (node (ref "R26") (pin "2") (pinfunction "2_2") (pintype "passive"))
    )
    (net (code "30") (name "Net-(LED5-PadA)") (class "Default")
      (node (ref "LED5") (pin "A") (pinfunction "A_A") (pintype "passive"))
      (node (ref "R18") (pin "1") (pinfunction "1_1") (pintype "passive"))
    )
    (net (code "31") (name "Net-(LED6-PadA)") (class "Default")
      (node (ref "LED6") (pin "A") (pinfunction "A_A") (pintype "passive"))
      (node (ref "R17") (pin "1") (pinfunction "1_1") (pintype "passive"))
    )
    (net (code "32") (name "Net-(R6-Pad1)") (class "Default")
      (node (ref "R6") (pin "1") (pinfunction "1_1") (pintype "passive"))
      (node (ref "R9") (pin "2") (pinfunction "2_2") (pintype "passive"))
      (node (ref "U$1") (pin "DIN") (pinfunction "DIN_DIN") (pintype "input"))
    )
    (net (code "33") (name "Net-(R10-Pad2)") (class "Default")
      (node (ref "R10") (pin "2") (pinfunction "2_2") (pintype "passive"))
      (node (ref "U$2") (pin "SIM_RST") (pinfunction "SIM_RST_SIM_RST") (pintype "bidirectional"))
    )
    (net (code "34") (name "Net-(R11-Pad2)") (class "Default")
      (node (ref "R11") (pin "2") (pinfunction "2_2") (pintype "passive"))
      (node (ref "U$2") (pin "SIM_CLK") (pinfunction "SIM_CLK_SIM_CLK") (pintype "bidirectional"))
    )
    (net (code "35") (name "Net-(R23-Pad1)") (class "Default")
      (node (ref "R23") (pin "1") (pinfunction "1_1") (pintype "passive"))
      (node (ref "R8") (pin "1") (pinfunction "1_1") (pintype "passive"))
      (node (ref "U$1") (pin "CS") (pinfunction "CS_CS") (pintype "bidirectional"))
    )
    (net (code "36") (name "Net-(R24-Pad2)") (class "Default")
      (node (ref "R24") (pin "2") (pinfunction "2_2") (pintype "passive"))
      (node (ref "R7") (pin "1") (pinfunction "1_1") (pintype "passive"))
      (node (ref "U$1") (pin "SCK") (pinfunction "SCK_SCK") (pintype "bidirectional"))
    )
    (net (code "37") (name "Net-(R35-Pad2)") (class "Default")
      (node (ref "R35") (pin "2") (pinfunction "2_2") (pintype "passive"))
      (node (ref "U$1") (pin "DOUT") (pinfunction "DOUT_DOUT") (pintype "output"))
    )
    (net (code "38") (name "Net-(R47-Pad2)") (class "Default")
      (node (ref "R47") (pin "2") (pinfunction "2_2") (pintype "passive"))
      (node (ref "U$2") (pin "SIM_DATA") (pinfunction "SIM_DATA_SIM_DATA") (pintype "bidirectional"))
    )
    (net (code "39") (name "Net-(T1-B)") (class "Default")
      (node (ref "R4") (pin "1") (pinfunction "1_1") (pintype "passive"))
      (node (ref "T1") (pin "1") (pinfunction "B_1") (pintype "passive"))
    )
    (net (code "40") (name "Net-(T1-C)") (class "Default")
      (node (ref "T1") (pin "3") (pinfunction "C_3") (pintype "passive"))
      (node (ref "U2") (pin "10") (pinfunction "PWRKEY_10") (pintype "input"))
    )
    (net (code "41") (name "Net-(T3-B)") (class "Default")
      (node (ref "JP10") (pin "1") (pinfunction "1_1") (pintype "passive"))
      (node (ref "T3") (pin "1") (pinfunction "B_1") (pintype "passive"))
    )
    (net (code "42") (name "Net-(T3-E)") (class "Default")
      (node (ref "R42") (pin "1") (pinfunction "1_1") (pintype "passive"))
      (node (ref "T3") (pin "2") (pinfunction "E_2") (pintype "passive"))
    )
    (net (code "43") (name "Net-(U1-(A10)PC2)") (class "Default")
      (node (ref "R27") (pin "2") (pinfunction "2_2") (pintype "passive"))
      (node (ref "U1") (pin "55") (pinfunction "(A10)PC2_55") (pintype "bidirectional"))
    )
    (net (code "44") (name "Net-(U1-(AD0)PA0)") (class "Default")
      (node (ref "R4") (pin "2") (pinfunction "2_2") (pintype "passive"))
      (node (ref "U1") (pin "78") (pinfunction "(AD0)PA0_78") (pintype "bidirectional"))
    )
    (net (code "45") (name "Net-(U1-(AD3)PA3)") (class "Default")
      (node (ref "R22") (pin "2") (pinfunction "2_2") (pintype "passive"))
      (node (ref "R36") (pin "1") (pinfunction "1_1") (pintype "passive"))
      (node (ref "U1") (pin "75") (pinfunction "(AD3)PA3_75") (pintype "bidirectional"))
    )
    (net (code "46") (name "Net-(U1-(AD4)PA4)") (class "Default")
      (node (ref "R19") (pin "2") (pinfunction "2_2") (pintype "passive"))
      (node (ref "R34") (pin "1") (pinfunction "1_1") (pintype "passive"))
      (node (ref "U1") (pin "74") (pinfunction "(AD4)PA4_74") (pintype "bidirectional"))
    )
    (net (code "47") (name "Net-(U1-(ADC1)PF1)") (class "Default")
      (node (ref "R20") (pin "1") (pinfunction "1_1") (pintype "passive"))
      (node (ref "R31") (pin "2") (pinfunction "2_2") (pintype "passive"))
      (node (ref "U1") (pin "96") (pinfunction "(ADC1)PF1_96") (pintype "bidirectional"))
    )
    (net (code "48") (name "Net-(U1-(ADC3)PF3)") (class "Default")
      (node (ref "DC17") (pin "1") (pinfunction "1_1") (pintype "passive"))
      (node (ref "R21") (pin "2") (pinfunction "2_2") (pintype "passive"))
      (node (ref "U1") (pin "94") (pinfunction "(ADC3)PF3_94") (pintype "bidirectional"))
    )
    (net (code "49") (name "Net-(U1-(MISO{slash}PCINT3)PB3)") (class "Default")
      (node (ref "JP4") (pin "1") (pinfunction "1_1") (pintype "passive"))
      (node (ref "R35") (pin "1") (pinfunction "1_1") (pintype "passive"))
      (node (ref "U1") (pin "22") (pinfunction "(MISO/PCINT3)PB3_22") (pintype "bidirectional"))
    )
    (net (code "50") (name "Net-(U1-(MOSI{slash}PCINT2)PB2)") (class "Default")
      (node (ref "JP4") (pin "3") (pinfunction "3_3") (pintype "passive"))
      (node (ref "R6") (pin "2") (pinfunction "2_2") (pintype "passive"))
      (node (ref "U1") (pin "21") (pinfunction "(MOSI/PCINT2)PB2_21") (pintype "bidirectional"))
    )
    (net (code "51") (name "Net-(U1-(OC0B)PG5)") (class "Default")
      (node (ref "R39") (pin "1") (pinfunction "1_1") (pintype "passive"))
      (node (ref "R40") (pin "2") (pinfunction "2_2") (pintype "passive"))
      (node (ref "U1") (pin "1") (pinfunction "(OC0B)PG5_1") (pintype "bidirectional"))
    )
    (net (code "52") (name "Net-(U1-(OC1B{slash}PCINT6)PB6)") (class "Default")
      (node (ref "R25") (pin "2") (pinfunction "2_2") (pintype "passive"))
      (node (ref "U1") (pin "25") (pinfunction "(OC1B/PCINT6)PB6_25") (pintype "bidirectional"))
    )
    (net (code "53") (name "Net-(U1-(RXD0{slash}PCIN8)PE0)") (class "Default")
      (node (ref "JP5") (pin "4") (pinfunction "4_4") (pintype "passive"))
      (node (ref "U1") (pin "2") (pinfunction "(RXD0/PCIN8)PE0_2") (pintype "bidirectional"))
    )
    (net (code "54") (name "Net-(U1-(RXD1{slash}INT2)PD2)") (class "Default")
      (node (ref "R15") (pin "2") (pinfunction "2_2") (pintype "passive"))
      (node (ref "U1") (pin "45") (pinfunction "(RXD1/INT2)PD2_45") (pintype "bidirectional"))
    )
    (net (code "55") (name "Net-(U1-(SCK{slash}PCINT1)PB1)") (class "Default")
      (node (ref "JP4") (pin "5") (pinfunction "5_5") (pintype "passive"))
      (node (ref "R7") (pin "2") (pinfunction "2_2") (pintype "passive"))
      (node (ref "U1") (pin "20") (pinfunction "(SCK/PCINT1)PB1_20") (pintype "bidirectional"))
    )
    (net (code "56") (name "Net-(U1-(SCL{slash}INT0)PD0)") (class "Default")
      (node (ref "R30") (pin "1") (pinfunction "1_1") (pintype "passive"))
      (node (ref "U1") (pin "43") (pinfunction "(SCL/INT0)PD0_43") (pintype "bidirectional"))
    )
    (net (code "57") (name "Net-(U1-(SDA{slash}INT1)PD1)") (class "Default")
      (node (ref "R5") (pin "1") (pinfunction "1_1") (pintype "passive"))
      (node (ref "U1") (pin "44") (pinfunction "(SDA/INT1)PD1_44") (pintype "bidirectional"))
    )
    (net (code "58") (name "Net-(U1-(SS{slash}PCINT0)PB0)") (class "Default")
      (node (ref "R8") (pin "2") (pinfunction "2_2") (pintype "passive"))
      (node (ref "U1") (pin "19") (pinfunction "(SS/PCINT0)PB0_19") (pintype "bidirectional"))
    )
    (net (code "59") (name "Net-(U1-(TXD0)PE1)") (class "Default")
      (node (ref "JP5") (pin "3") (pinfunction "3_3") (pintype "passive"))
      (node (ref "U1") (pin "3") (pinfunction "(TXD0)PE1_3") (pintype "bidirectional"))
    )
    (net (code "60") (name "Net-(U1-(TXD1{slash}INT3)PD3)") (class "Default")
      (node (ref "R14") (pin "2") (pinfunction "2_2") (pintype "passive"))
      (node (ref "U1") (pin "46") (pinfunction "(TXD1/INT3)PD3_46") (pintype "bidirectional"))
    )
    (net (code "61") (name "Net-(U1-(WR)PG0)") (class "Default")
      (node (ref "R28") (pin "2") (pinfunction "2_2") (pintype "passive"))
      (node (ref "U1") (pin "51") (pinfunction "(WR)PG0_51") (pintype "bidirectional"))
    )
    (net (code "62") (name "Net-(U1-PJ0(RXD3{slash}PCINT9))") (class "Default")
      (node (ref "R32") (pin "1") (pinfunction "1_1") (pintype "passive"))
      (node (ref "U1") (pin "63") (pinfunction "PJ0(RXD3/PCINT9)_63") (pintype "bidirectional"))
    )
    (net (code "63") (name "Net-(U1-PJ1(TXD3{slash}PCINT10))") (class "Default")
      (node (ref "R33") (pin "1") (pinfunction "1_1") (pintype "passive"))
      (node (ref "U1") (pin "64") (pinfunction "PJ1(TXD3/PCINT10)_64") (pintype "bidirectional"))
    )
    (net (code "64") (name "Net-(U1-PK3(ADC11{slash}PCINT19))") (class "Default")
      (node (ref "R2") (pin "2") (pinfunction "2_2") (pintype "passive"))
      (node (ref "R3") (pin "2") (pinfunction "2_2") (pintype "passive"))
      (node (ref "U1") (pin "86") (pinfunction "PK3(ADC11/PCINT19)_86") (pintype "bidirectional"))
    )
    (net (code "65") (name "Net-(U1-PK4(ADC12{slash}PCINT20))") (class "Default")
      (node (ref "DC14") (pin "2") (pinfunction "2_2") (pintype "passive"))
      (node (ref "R42") (pin "2") (pinfunction "2_2") (pintype "passive"))
      (node (ref "U1") (pin "85") (pinfunction "PK4(ADC12/PCINT20)_85") (pintype "bidirectional"))
    )
    (net (code "66") (name "Net-(U1-PK5(ADC13{slash}PCINT21))") (class "Default")
      (node (ref "JP18") (pin "1") (pinfunction "1_1") (pintype "passive"))
      (node (ref "U1") (pin "84") (pinfunction "PK5(ADC13/PCINT21)_84") (pintype "bidirectional"))
    )
    (net (code "67") (name "Net-(U1-PK6(ADC14{slash}PCINT22))") (class "Default")
      (node (ref "R43") (pin "2") (pinfunction "2_2") (pintype "passive"))
      (node (ref "R44") (pin "2") (pinfunction "2_2") (pintype "passive"))
      (node (ref "U1") (pin "83") (pinfunction "PK6(ADC14/PCINT22)_83") (pintype "bidirectional"))
    )
    (net (code "68") (name "Net-(U1-PK7(ADC15{slash}PCINT23))") (class "Default")
      (node (ref "DC21") (pin "1") (pinfunction "1_1") (pintype "passive"))
      (node (ref "R1") (pin "1") (pinfunction "1_1") (pintype "passive"))
      (node (ref "U1") (pin "82") (pinfunction "PK7(ADC15/PCINT23)_82") (pintype "bidirectional"))
    )
    (net (code "69") (name "Net-(U1-RESET)") (class "Default")
      (node (ref "D2") (pin "A") (pinfunction "A_A") (pintype "passive"))
      (node (ref "DC11") (pin "1") (pinfunction "1_1") (pintype "passive"))
      (node (ref "JP4") (pin "2") (pinfunction "2_2") (pintype "passive"))
      (node (ref "JP5") (pin "2") (pinfunction "2_2") (pintype "passive"))
      (node (ref "R16") (pin "2") (pinfunction "2_2") (pintype "passive"))
      (node (ref "U1") (pin "30") (pinfunction "RESET_30") (pintype "input"))
    )
    (net (code "70") (name "Net-(U1-XTAL1)") (class "Default")
      (node (ref "C8") (pin "2") (pinfunction "2_2") (pintype "passive"))
      (node (ref "O1") (pin "1") (pinfunction "1_1") (pintype "passive"))
      (node (ref "U1") (pin "34") (pinfunction "XTAL1_34") (pintype "input"))
    )
    (net (code "71") (name "Net-(U1-XTAL2)") (class "Default")
      (node (ref "C7") (pin "2") (pinfunction "2_2") (pintype "passive"))
      (node (ref "O1") (pin "2") (pinfunction "2_2") (pintype "passive"))
      (node (ref "U1") (pin "33") (pinfunction "XTAL2_33") (pintype "output"))
    )
    (net (code "72") (name "Net-(U2-NETLIGHT)") (class "Default")
      (node (ref "R17") (pin "2") (pinfunction "2_2") (pintype "passive"))
      (node (ref "U2") (pin "13") (pinfunction "NETLIGHT_13") (pintype "output"))
    )
    (net (code "73") (name "Net-(U2-RF_ANT)") (class "Default")
      (node (ref "U2") (pin "39") (pinfunction "RF_ANT_39") (pintype "bidirectional"))
      (node (ref "X1") (pin "1") (pinfunction "1_1") (pintype "passive"))
    )
    (net (code "74") (name "Net-(U2-RI)") (class "Default")
      (node (ref "D2") (pin "K") (pinfunction "K_K") (pintype "passive"))
      (node (ref "U2") (pin "26") (pinfunction "RI_26") (pintype "output"))
    )
    (net (code "75") (name "Net-(U2-RXD)") (class "Default")
      (node (ref "R14") (pin "1") (pinfunction "1_1") (pintype "passive"))
      (node (ref "R29") (pin "2") (pinfunction "2_2") (pintype "passive"))
      (node (ref "U2") (pin "21") (pinfunction "RXD_21") (pintype "input"))
    )
    (net (code "76") (name "Net-(U2-SIM_CLK)") (class "Default")
      (node (ref "R11") (pin "1") (pinfunction "1_1") (pintype "passive"))
      (node (ref "U2") (pin "30") (pinfunction "SIM_CLK_30") (pintype "output"))
    )
    (net (code "77") (name "Net-(U2-SIM_DATA)") (class "Default")
      (node (ref "R47") (pin "1") (pinfunction "1_1") (pintype "passive"))
      (node (ref "U2") (pin "29") (pinfunction "SIM_DATA_29") (pintype "bidirectional"))
    )
    (net (code "78") (name "Net-(U2-SIM_GND)") (class "Default")
      (node (ref "DC15") (pin "1") (pinfunction "1_1") (pintype "passive"))
      (node (ref "U$2") (pin "SIM_GND") (pinfunction "SIM_GND_SIM_GND") (pintype "bidirectional"))
      (node (ref "U2") (pin "31") (pinfunction "SIM_GND_31") (pintype "power_in"))
    )
    (net (code "79") (name "Net-(U2-SIM_RST)") (class "Default")
      (node (ref "R10") (pin "1") (pinfunction "1_1") (pintype "passive"))
      (node (ref "U2") (pin "28") (pinfunction "SIM_RST_28") (pintype "output"))
    )
    (net (code "80") (name "Net-(U2-SIM_VDD)") (class "Default")
      (node (ref "DC15") (pin "2") (pinfunction "2_2") (pintype "passive"))
      (node (ref "U$2") (pin "SIM_VDD") (pinfunction "SIM_VDD_SIM_VDD") (pintype "bidirectional"))
      (node (ref "U2") (pin "27") (pinfunction "SIM_VDD_27") (pintype "power_in"))
    )
    (net (code "81") (name "Net-(U2-TXD)") (class "Default")
      (node (ref "R15") (pin "1") (pinfunction "1_1") (pintype "passive"))
      (node (ref "U2") (pin "22") (pinfunction "TXD_22") (pintype "output"))
    )
    (net (code "82") (name "VDD") (class "Default")
      (node (ref "DC1") (pin "1") (pinfunction "1_1") (pintype "passive"))
      (node (ref "DC18") (pin "2") (pinfunction "2_2") (pintype "passive"))
      (node (ref "DC2") (pin "1") (pinfunction "1_1") (pintype "passive"))
      (node (ref "DC3") (pin "1") (pinfunction "1_1") (pintype "passive"))
      (node (ref "DC4") (pin "1") (pinfunction "1_1") (pintype "passive"))
      (node (ref "DC5") (pin "1") (pinfunction "1_1") (pintype "passive"))
      (node (ref "L1") (pin "2") (pinfunction "2_2") (pintype "passive"))
      (node (ref "R20") (pin "2") (pinfunction "2_2") (pintype "passive"))
      (node (ref "R40") (pin "1") (pinfunction "1_1") (pintype "passive"))
      (node (ref "U1") (pin "10") (pinfunction "VCC_10") (pintype "power_in"))
      (node (ref "U1") (pin "100") (pinfunction "AVCC_100") (pintype "power_in"))
      (node (ref "U1") (pin "31") (pinfunction "VCC1_31") (pintype "power_in"))
      (node (ref "U1") (pin "61") (pinfunction "VCC2_61") (pintype "power_in"))
      (node (ref "U1") (pin "80") (pinfunction "VCC3_80") (pintype "power_in"))
    )
    (net (code "83") (name "unconnected-(IC3-I+_1-Pad2)") (class "Default")
      (node (ref "IC3") (pin "2") (pinfunction "I+_1_2") (pintype "bidirectional"))
    )
    (net (code "84") (name "unconnected-(IC3-I-_0-Pad3)") (class "Default")
      (node (ref "IC3") (pin "3") (pinfunction "I-_0_3") (pintype "bidirectional"))
    )
    (net (code "85") (name "unconnected-(U$1-PadCD)") (class "Default")
      (node (ref "U$1") (pin "CD") (pinfunction "CD_CD") (pintype "output"))
    )
    (net (code "86") (name "unconnected-(U1-(A8)PC0-Pad53)") (class "Default")
      (node (ref "U1") (pin "53") (pinfunction "(A8)PC0_53") (pintype "bidirectional"))
    )
    (net (code "87") (name "unconnected-(U1-(A9)PC1-Pad54)") (class "Default")
      (node (ref "U1") (pin "54") (pinfunction "(A9)PC1_54") (pintype "bidirectional"))
    )
    (net (code "88") (name "unconnected-(U1-(A11)PC3-Pad56)") (class "Default")
      (node (ref "U1") (pin "56") (pinfunction "(A11)PC3_56") (pintype "bidirectional"))
    )
    (net (code "89") (name "unconnected-(U1-(A12)PC4-Pad57)") (class "Default")
      (node (ref "U1") (pin "57") (pinfunction "(A12)PC4_57") (pintype "bidirectional"))
    )
    (net (code "90") (name "unconnected-(U1-(A13)PC5-Pad58)") (class "Default")
      (node (ref "U1") (pin "58") (pinfunction "(A13)PC5_58") (pintype "bidirectional"))
    )
    (net (code "91") (name "unconnected-(U1-(A14)PC6-Pad59)") (class "Default")
      (node (ref "U1") (pin "59") (pinfunction "(A14)PC6_59") (pintype "bidirectional"))
    )
    (net (code "92") (name "unconnected-(U1-(A15)PC7-Pad60)") (class "Default")
      (node (ref "U1") (pin "60") (pinfunction "(A15)PC7_60") (pintype "bidirectional"))
    )
    (net (code "93") (name "unconnected-(U1-(AD1)PA1-Pad77)") (class "Default")
      (node (ref "U1") (pin "77") (pinfunction "(AD1)PA1_77") (pintype "bidirectional"))
    )
    (net (code "94") (name "unconnected-(U1-(AD2)PA2-Pad76)") (class "Default")
      (node (ref "U1") (pin "76") (pinfunction "(AD2)PA2_76") (pintype "bidirectional"))
    )
    (net (code "95") (name "unconnected-(U1-(AD5)PA5-Pad73)") (class "Default")
      (node (ref "U1") (pin "73") (pinfunction "(AD5)PA5_73") (pintype "bidirectional"))
    )
    (net (code "96") (name "unconnected-(U1-(AD6)PA6-Pad72)") (class "Default")
      (node (ref "U1") (pin "72") (pinfunction "(AD6)PA6_72") (pintype "bidirectional"))
    )
    (net (code "97") (name "unconnected-(U1-(AD7)PA7-Pad71)") (class "Default")
      (node (ref "U1") (pin "71") (pinfunction "(AD7)PA7_71") (pintype "bidirectional"))
    )
    (net (code "98") (name "unconnected-(U1-(ADC0)PF0-Pad97)") (class "Default")
      (node (ref "U1") (pin "97") (pinfunction "(ADC0)PF0_97") (pintype "bidirectional"))
    )
    (net (code "99") (name "unconnected-(U1-(ADC2)PF2-Pad95)") (class "Default")
      (node (ref "U1") (pin "95") (pinfunction "(ADC2)PF2_95") (pintype "bidirectional"))
    )
    (net (code "100") (name "unconnected-(U1-(ADC4{slash}TCK)PF4-Pad93)") (class "Default")
      (node (ref "U1") (pin "93") (pinfunction "(ADC4/TCK)PF4_93") (pintype "bidirectional"))
    )
    (net (code "101") (name "unconnected-(U1-(ADC5{slash}TMS)PF5-Pad92)") (class "Default")
      (node (ref "U1") (pin "92") (pinfunction "(ADC5/TMS)PF5_92") (pintype "bidirectional"))
    )
    (net (code "102") (name "unconnected-(U1-(ADC6{slash}TDO)PF6-Pad91)") (class "Default")
      (node (ref "U1") (pin "91") (pinfunction "(ADC6/TDO)PF6_91") (pintype "bidirectional"))
    )
    (net (code "103") (name "unconnected-(U1-(ADC7{slash}TDI)PF7-Pad90)") (class "Default")
      (node (ref "U1") (pin "90") (pinfunction "(ADC7/TDI)PF7_90") (pintype "bidirectional"))
    )
    (net (code "104") (name "unconnected-(U1-(ALE)PG2-Pad70)") (class "Default")
      (node (ref "U1") (pin "70") (pinfunction "(ALE)PG2_70") (pintype "bidirectional"))
    )
    (net (code "105") (name "unconnected-(U1-(CLKO{slash}ICP3{slash}INT7)PE7-Pad9)") (class "Default")
      (node (ref "U1") (pin "9") (pinfunction "(CLKO/ICP3/INT7)PE7_9") (pintype "bidirectional"))
    )
    (net (code "106") (name "unconnected-(U1-(ICP1)PD4-Pad47)") (class "Default")
      (node (ref "U1") (pin "47") (pinfunction "(ICP1)PD4_47") (pintype "bidirectional"))
    )
    (net (code "107") (name "unconnected-(U1-(OC0A{slash}OC1C{slash}PCINT7)PB7-Pad26)") (class "Default")
      (node (ref "U1") (pin "26") (pinfunction "(OC0A/OC1C/PCINT7)PB7_26") (pintype "bidirectional"))
    )
    (net (code "108") (name "unconnected-(U1-(OC1A{slash}PCINT5)PB5-Pad24)") (class "Default")
      (node (ref "U1") (pin "24") (pinfunction "(OC1A/PCINT5)PB5_24") (pintype "bidirectional"))
    )
    (net (code "109") (name "unconnected-(U1-(OC2A{slash}PCINT4)PB4-Pad23)") (class "Default")
      (node (ref "U1") (pin "23") (pinfunction "(OC2A/PCINT4)PB4_23") (pintype "bidirectional"))
    )
    (net (code "110") (name "unconnected-(U1-(OC3A{slash}AIN1)PE3-Pad5)") (class "Default")
      (node (ref "U1") (pin "5") (pinfunction "(OC3A/AIN1)PE3_5") (pintype "bidirectional"))
    )
    (net (code "111") (name "unconnected-(U1-(OC3B{slash}INT4)PE4-Pad6)") (class "Default")
      (node (ref "U1") (pin "6") (pinfunction "(OC3B/INT4)PE4_6") (pintype "bidirectional"))
    )
    (net (code "112") (name "unconnected-(U1-(OC3C{slash}INT5)PE5-Pad7)") (class "Default")
      (node (ref "U1") (pin "7") (pinfunction "(OC3C/INT5)PE5_7") (pintype "bidirectional"))
    )
    (net (code "113") (name "unconnected-(U1-(RD)PG1-Pad52)") (class "Default")
      (node (ref "U1") (pin "52") (pinfunction "(RD)PG1_52") (pintype "bidirectional"))
    )
    (net (code "114") (name "unconnected-(U1-(T0)PD7-Pad50)") (class "Default")
      (node (ref "U1") (pin "50") (pinfunction "(T0)PD7_50") (pintype "bidirectional"))
    )
    (net (code "115") (name "unconnected-(U1-(T1)PD6-Pad49)") (class "Default")
      (node (ref "U1") (pin "49") (pinfunction "(T1)PD6_49") (pintype "bidirectional"))
    )
    (net (code "116") (name "unconnected-(U1-(T3{slash}INT6)PE6-Pad8)") (class "Default")
      (node (ref "U1") (pin "8") (pinfunction "(T3/INT6)PE6_8") (pintype "bidirectional"))
    )
    (net (code "117") (name "unconnected-(U1-(TOSC1)PG4-Pad29)") (class "Default")
      (node (ref "U1") (pin "29") (pinfunction "(TOSC1)PG4_29") (pintype "bidirectional"))
    )
    (net (code "118") (name "unconnected-(U1-(TOSC2)PG3-Pad28)") (class "Default")
      (node (ref "U1") (pin "28") (pinfunction "(TOSC2)PG3_28") (pintype "bidirectional"))
    )
    (net (code "119") (name "unconnected-(U1-(XCK0{slash}AIN0)PE2-Pad4)") (class "Default")
      (node (ref "U1") (pin "4") (pinfunction "(XCK0/AIN0)PE2_4") (pintype "bidirectional"))
    )
    (net (code "120") (name "unconnected-(U1-(XCK1)PD5-Pad48)") (class "Default")
      (node (ref "U1") (pin "48") (pinfunction "(XCK1)PD5_48") (pintype "bidirectional"))
    )
    (net (code "121") (name "unconnected-(U1-AREF-Pad98)") (class "Default")
      (node (ref "U1") (pin "98") (pinfunction "AREF_98") (pintype "bidirectional"))
    )
    (net (code "122") (name "unconnected-(U1-PH0(RXD2)-Pad12)") (class "Default")
      (node (ref "U1") (pin "12") (pinfunction "PH0(RXD2)_12") (pintype "bidirectional"))
    )
    (net (code "123") (name "unconnected-(U1-PH1(TXD2)-Pad13)") (class "Default")
      (node (ref "U1") (pin "13") (pinfunction "PH1(TXD2)_13") (pintype "bidirectional"))
    )
    (net (code "124") (name "unconnected-(U1-PH2(XCK2)-Pad14)") (class "Default")
      (node (ref "U1") (pin "14") (pinfunction "PH2(XCK2)_14") (pintype "bidirectional"))
    )
    (net (code "125") (name "unconnected-(U1-PH3(OC4A)-Pad15)") (class "Default")
      (node (ref "U1") (pin "15") (pinfunction "PH3(OC4A)_15") (pintype "bidirectional"))
    )
    (net (code "126") (name "unconnected-(U1-PH4(OC4B)-Pad16)") (class "Default")
      (node (ref "U1") (pin "16") (pinfunction "PH4(OC4B)_16") (pintype "bidirectional"))
    )
    (net (code "127") (name "unconnected-(U1-PH5(OC4C)-Pad17)") (class "Default")
      (node (ref "U1") (pin "17") (pinfunction "PH5(OC4C)_17") (pintype "bidirectional"))
    )
    (net (code "128") (name "unconnected-(U1-PH6(OC2B)-Pad18)") (class "Default")
      (node (ref "U1") (pin "18") (pinfunction "PH6(OC2B)_18") (pintype "bidirectional"))
    )
    (net (code "129") (name "unconnected-(U1-PH7(T4)-Pad27)") (class "Default")
      (node (ref "U1") (pin "27") (pinfunction "PH7(T4)_27") (pintype "bidirectional"))
    )
    (net (code "130") (name "unconnected-(U1-PJ2(XCK3{slash}PCINT11)-Pad65)") (class "Default")
      (node (ref "U1") (pin "65") (pinfunction "PJ2(XCK3/PCINT11)_65") (pintype "bidirectional"))
    )
    (net (code "131") (name "unconnected-(U1-PJ3(PCINT12)-Pad66)") (class "Default")
      (node (ref "U1") (pin "66") (pinfunction "PJ3(PCINT12)_66") (pintype "bidirectional"))
    )
    (net (code "132") (name "unconnected-(U1-PJ4(PCINT13)-Pad67)") (class "Default")
      (node (ref "U1") (pin "67") (pinfunction "PJ4(PCINT13)_67") (pintype "bidirectional"))
    )
    (net (code "133") (name "unconnected-(U1-PJ5(PCINT14)-Pad68)") (class "Default")
      (node (ref "U1") (pin "68") (pinfunction "PJ5(PCINT14)_68") (pintype "bidirectional"))
    )
    (net (code "134") (name "unconnected-(U1-PJ6(PCINT15)-Pad69)") (class "Default")
      (node (ref "U1") (pin "69") (pinfunction "PJ6(PCINT15)_69") (pintype "bidirectional"))
    )
    (net (code "135") (name "unconnected-(U1-PJ7-Pad79)") (class "Default")
      (node (ref "U1") (pin "79") (pinfunction "PJ7_79") (pintype "bidirectional"))
    )
    (net (code "136") (name "unconnected-(U1-PK0(ADC8{slash}PCINT16)-Pad89)") (class "Default")
      (node (ref "U1") (pin "89") (pinfunction "PK0(ADC8/PCINT16)_89") (pintype "bidirectional"))
    )
    (net (code "137") (name "unconnected-(U1-PK1(ADC9{slash}PCINT17)-Pad88)") (class "Default")
      (node (ref "U1") (pin "88") (pinfunction "PK1(ADC9/PCINT17)_88") (pintype "bidirectional"))
    )
    (net (code "138") (name "unconnected-(U1-PK2(ADC10{slash}PCINT18)-Pad87)") (class "Default")
      (node (ref "U1") (pin "87") (pinfunction "PK2(ADC10/PCINT18)_87") (pintype "bidirectional"))
    )
    (net (code "139") (name "unconnected-(U1-PL0(ICP4)-Pad35)") (class "Default")
      (node (ref "U1") (pin "35") (pinfunction "PL0(ICP4)_35") (pintype "bidirectional"))
    )
    (net (code "140") (name "unconnected-(U1-PL1(ICP5)-Pad36)") (class "Default")
      (node (ref "U1") (pin "36") (pinfunction "PL1(ICP5)_36") (pintype "bidirectional"))
    )
    (net (code "141") (name "unconnected-(U1-PL2(T5)-Pad37)") (class "Default")
      (node (ref "U1") (pin "37") (pinfunction "PL2(T5)_37") (pintype "bidirectional"))
    )
    (net (code "142") (name "unconnected-(U1-PL3(OC5A)-Pad38)") (class "Default")
      (node (ref "U1") (pin "38") (pinfunction "PL3(OC5A)_38") (pintype "bidirectional"))
    )
    (net (code "143") (name "unconnected-(U1-PL4(OC5B)-Pad39)") (class "Default")
      (node (ref "U1") (pin "39") (pinfunction "PL4(OC5B)_39") (pintype "bidirectional"))
    )
    (net (code "144") (name "unconnected-(U1-PL5(OC5C)-Pad40)") (class "Default")
      (node (ref "U1") (pin "40") (pinfunction "PL5(OC5C)_40") (pintype "bidirectional"))
    )
    (net (code "145") (name "unconnected-(U1-PL6-Pad41)") (class "Default")
      (node (ref "U1") (pin "41") (pinfunction "PL6_41") (pintype "bidirectional"))
    )
    (net (code "146") (name "unconnected-(U1-PL7-Pad42)") (class "Default")
      (node (ref "U1") (pin "42") (pinfunction "PL7_42") (pintype "bidirectional"))
    )
    (net (code "147") (name "unconnected-(U2-CTS-Pad23)") (class "Default")
      (node (ref "U2") (pin "23") (pinfunction "CTS_23") (pintype "output"))
    )
    (net (code "148") (name "unconnected-(U2-DBG_RXD-Pad14)") (class "Default")
      (node (ref "U2") (pin "14") (pinfunction "DBG_RXD_14") (pintype "input"))
    )
    (net (code "149") (name "unconnected-(U2-DBG_TXD-Pad15)") (class "Default")
      (node (ref "U2") (pin "15") (pinfunction "DBG_TXD_15") (pintype "output"))
    )
    (net (code "150") (name "unconnected-(U2-DCD-Pad25)") (class "Default")
      (node (ref "U2") (pin "25") (pinfunction "DCD_25") (pintype "output"))
    )
    (net (code "151") (name "unconnected-(U2-DTR-Pad20)") (class "Default")
      (node (ref "U2") (pin "20") (pinfunction "DTR_20") (pintype "input"))
    )
    (net (code "152") (name "unconnected-(U2-EMERG_OFF-Pad11)") (class "Default")
      (node (ref "U2") (pin "11") (pinfunction "EMERG_OFF_11") (pintype "input"))
    )
    (net (code "153") (name "unconnected-(U2-LOUDSPKN-Pad8)") (class "Default")
      (node (ref "U2") (pin "8") (pinfunction "LOUDSPKN_8") (pintype "output"))
    )
    (net (code "154") (name "unconnected-(U2-LOUDSPKP-Pad9)") (class "Default")
      (node (ref "U2") (pin "9") (pinfunction "LOUDSPKP_9") (pintype "output"))
    )
    (net (code "155") (name "unconnected-(U2-MIC1N-Pad5)") (class "Default")
      (node (ref "U2") (pin "5") (pinfunction "MIC1N_5") (pintype "input"))
    )
    (net (code "156") (name "unconnected-(U2-MIC1P-Pad4)") (class "Default")
      (node (ref "U2") (pin "4") (pinfunction "MIC1P_4") (pintype "input"))
    )
    (net (code "157") (name "unconnected-(U2-MIC2N-Pad3)") (class "Default")
      (node (ref "U2") (pin "3") (pinfunction "MIC2N_3") (pintype "input"))
    )
    (net (code "158") (name "unconnected-(U2-MIC2P-Pad2)") (class "Default")
      (node (ref "U2") (pin "2") (pinfunction "MIC2P_2") (pintype "input"))
    )
    (net (code "159") (name "unconnected-(U2-RTS-Pad24)") (class "Default")
      (node (ref "U2") (pin "24") (pinfunction "RTS_24") (pintype "input"))
    )
    (net (code "160") (name "unconnected-(U2-SPK1N-Pad6)") (class "Default")
      (node (ref "U2") (pin "6") (pinfunction "SPK1N_6") (pintype "output"))
    )
    (net (code "161") (name "unconnected-(U2-SPK1P-Pad7)") (class "Default")
      (node (ref "U2") (pin "7") (pinfunction "SPK1P_7") (pintype "output"))
    )
    (net (code "162") (name "unconnected-(U2-STATUS-Pad12)") (class "Default")
      (node (ref "U2") (pin "12") (pinfunction "STATUS_12") (pintype "output"))
    )
  )
)
